# Raspberry_Pi_CM4.net
KiCad netlist of a schematic drawn in Altium Designer
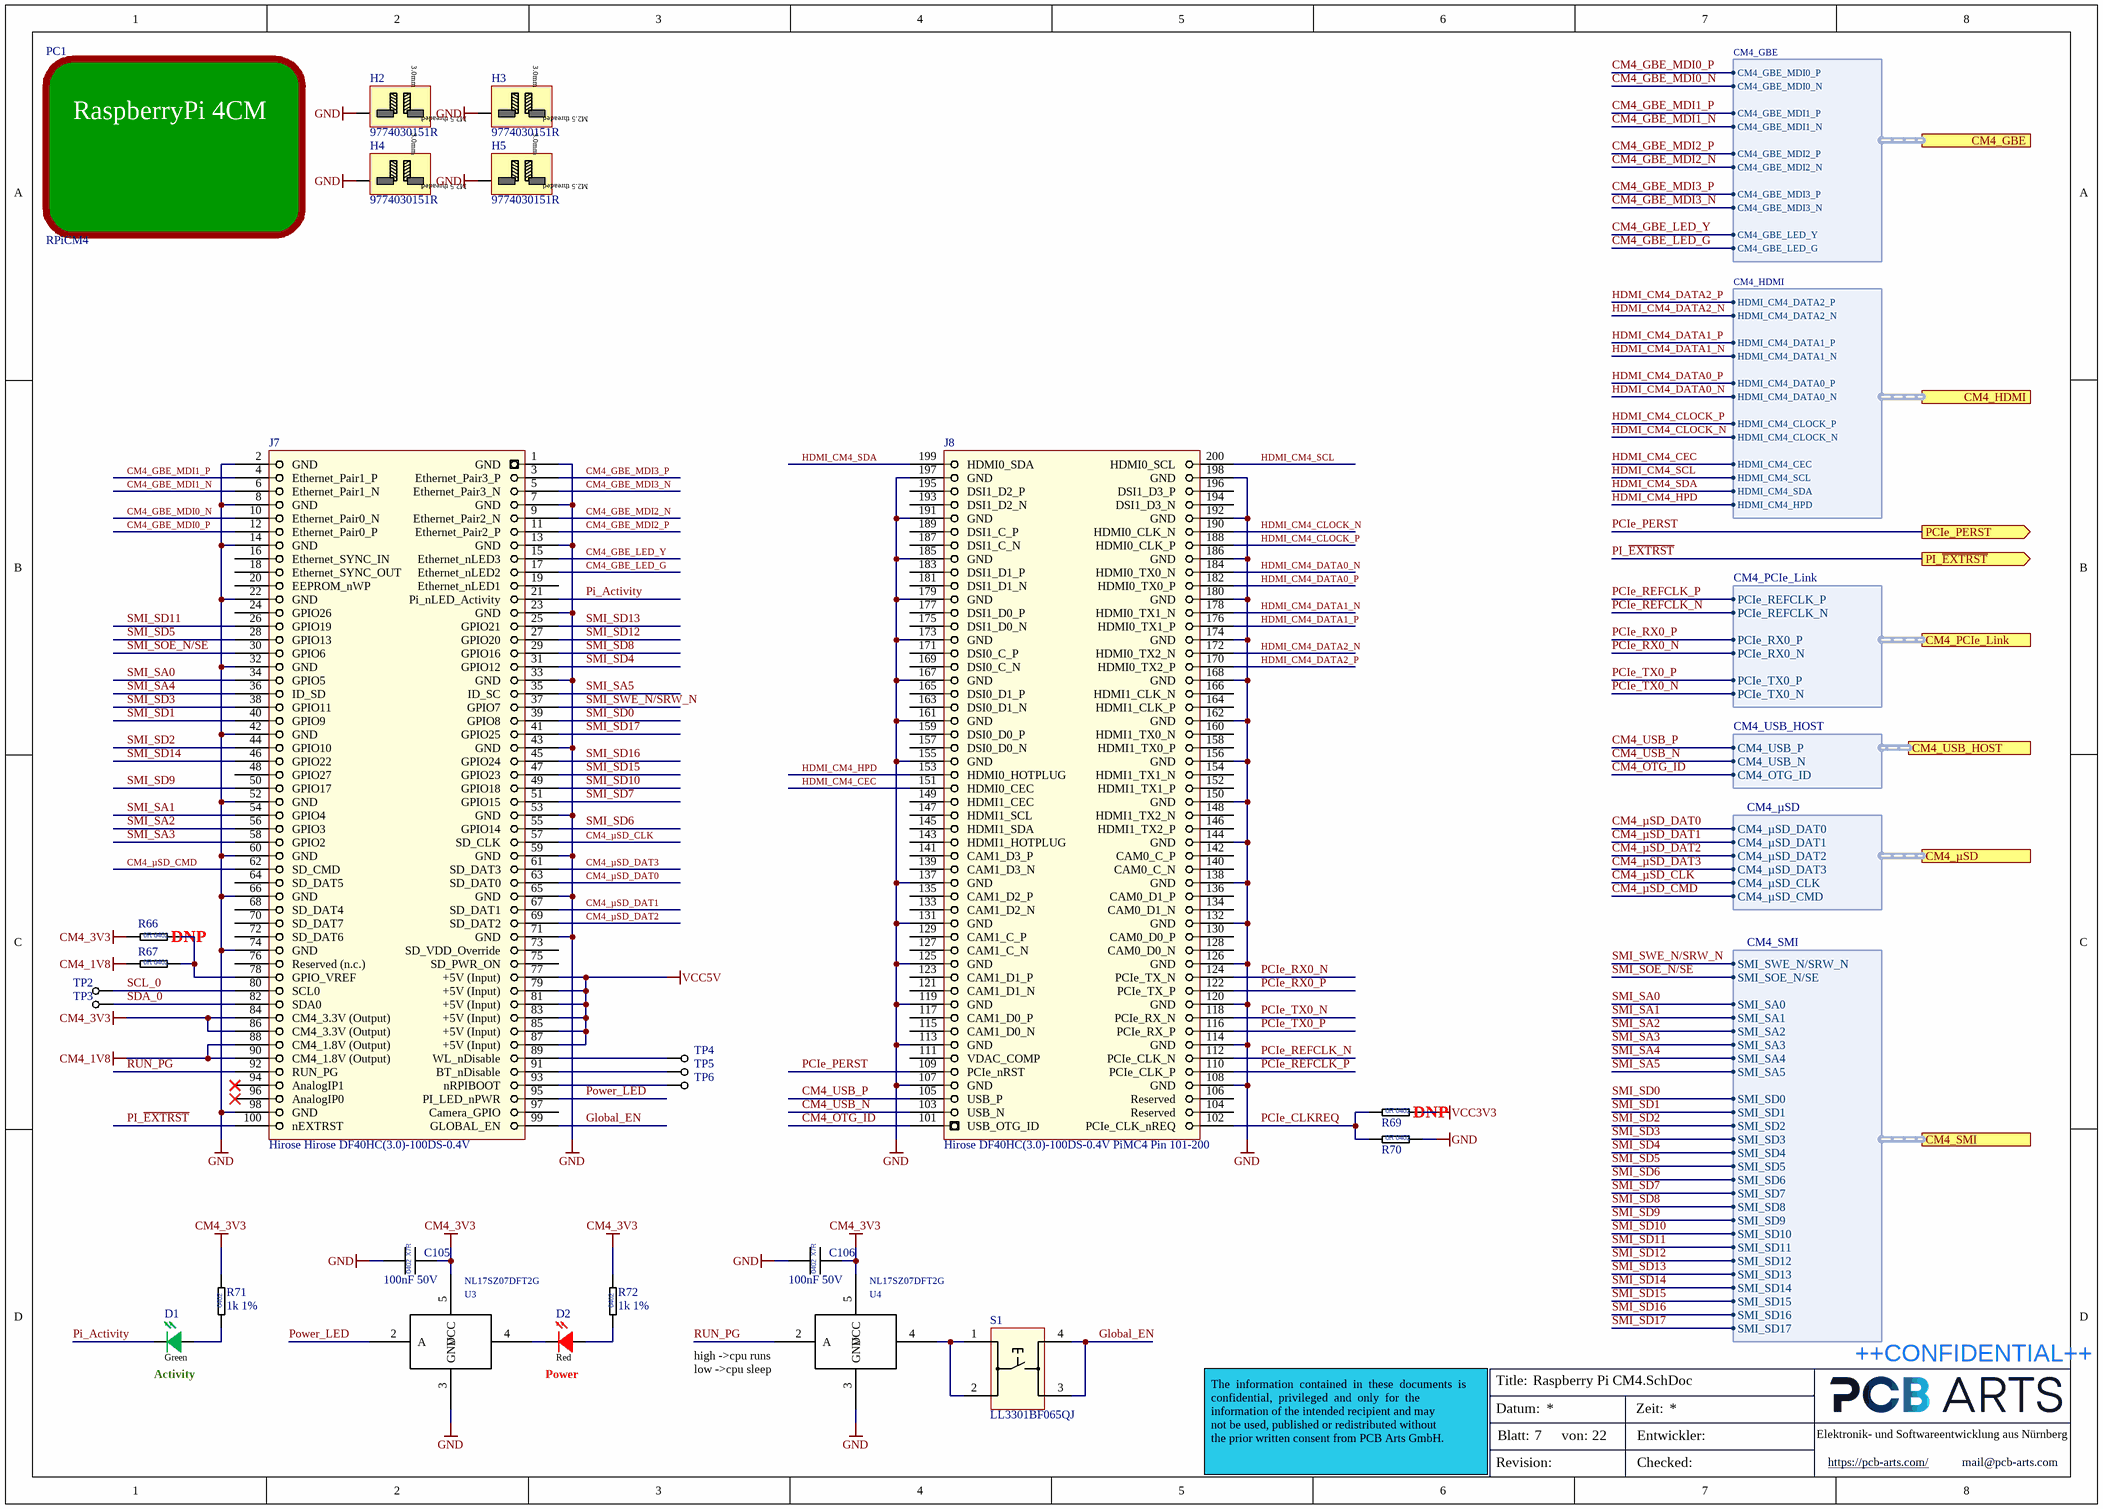
[diagram p0: Raspberry Pi CM4.SchDoc]

(export (version "E")
  (design (tool "Eeschema 10.0.6"))
  (components
    (comp (ref "C105")
      (value "100nF 50V")
      (footprint "Cap:CAP_0402_L")
      (description "Multilayer Ceramic Capacitors MLCC - SMD/SMT 0402 50VDC")
      (libsource (lib "Cap") (part "CAP_0402_100nF_50V"))
    )
    (comp (ref "C106")
      (value "100nF 50V")
      (footprint "Cap:CAP_0402_L")
      (description "Multilayer Ceramic Capacitors MLCC - SMD/SMT 0402 50VDC")
      (libsource (lib "Cap") (part "CAP_0402_100nF_50V"))
    )
    (comp (ref "D1")
      (value "LTST-S270KGKT")
      (footprint "Active:LED-0603 Sideview")
      (description "GREEN  0603 Light Emitting Diode")
      (fields (field (name "COLOR") "Green"))
      (libsource (lib "Active") (part "LED 0603 Green Sideview"))
    )
    (comp (ref "D2")
      (value "LTST-S270KRKT")
      (footprint "Active:LED-0603 Sideview")
      (description "RED  0603 Light Emitting Diode")
      (fields (field (name "COLOR") "Red"))
      (libsource (lib "Active") (part "LED 0603 Red Sideview"))
    )
    (comp (ref "H2")
      (value "9774030151R")
      (footprint "Electro_Mech:9774030151R")
      (description "Würth Standoff M2.5 h:3.0mm 9774030151R")
      (libsource (lib "Electro_Mech") (part "Würth Standoff M2.5 h{colon}3.0mm"))
    )
    (comp (ref "H3")
      (value "9774030151R")
      (footprint "Electro_Mech:9774030151R")
      (description "Würth Standoff M2.5 h:3.0mm 9774030151R")
      (libsource (lib "Electro_Mech") (part "Würth Standoff M2.5 h{colon}3.0mm"))
    )
    (comp (ref "H4")
      (value "9774030151R")
      (footprint "Electro_Mech:9774030151R")
      (description "Würth Standoff M2.5 h:3.0mm 9774030151R")
      (libsource (lib "Electro_Mech") (part "Würth Standoff M2.5 h{colon}3.0mm"))
    )
    (comp (ref "H5")
      (value "9774030151R")
      (footprint "Electro_Mech:9774030151R")
      (description "Würth Standoff M2.5 h:3.0mm 9774030151R")
      (libsource (lib "Electro_Mech") (part "Würth Standoff M2.5 h{colon}3.0mm"))
    )
    (comp (ref "J7")
      (value "Hirose Hirose DF40HC(3.0)-100DS-0.4V")
      (footprint "conn:Hirose DF40HC(3.0)-100DS-0.4V_1-100")
      (description "Hirose DF40HC(3.0)-100DS-0.4V 3mm heigth receptacle for Raspberry Pi CM4, Pin 1-100")
      (libsource (lib "Conn") (part "DF40HC(3.0)-100DS-0.4V RPiCM4 Pin 1-100"))
    )
    (comp (ref "J8")
      (value "Hirose DF40HC(3.0)-100DS-0.4V PiMC4 Pin 101-200")
      (footprint "Conn:Hirose DF40HC(3.0)-100DS-0.4V_101-200")
      (description "Hirose DF40C-100DS-0.4V 3mm heigth receptacle for Raspberry Pi CM4, Pin 101-200")
      (libsource (lib "Conn") (part "DF40HC(3.0)-100DS-0.4V RPiCM4 Pin 101-200"))
    )
    (comp (ref "PC1")
      (value "RPiCM4")
      (footprint "Mechanical:RaspberryPi_CM4")
      (description "Raspberry Pi 4 Compute Module 4")
      (libsource (lib "Mechanical") (part "Raspberry Pi Compute Module 4"))
    )
    (comp (ref "R66")
      (value "0R Jumper")
      (footprint "Res:RES_0402_L")
      (description "Thick Film Resistors - SMD 0Ohm")
      (libsource (lib "Res") (part "RES_0402_0R Jumper"))
    )
    (comp (ref "R67")
      (value "0R Jumper")
      (footprint "Res:RES_0402_L")
      (description "Thick Film Resistors - SMD 0Ohm")
      (libsource (lib "Res") (part "RES_0402_0R Jumper"))
    )
    (comp (ref "R69")
      (value "0R Jumper")
      (footprint "Res:RES_0402_L")
      (description "Thick Film Resistors - SMD 0Ohm")
      (libsource (lib "Res") (part "RES_0402_0R Jumper"))
    )
    (comp (ref "R70")
      (value "0R Jumper")
      (footprint "Res:RES_0402_L")
      (description "Thick Film Resistors - SMD 0Ohm")
      (libsource (lib "Res") (part "RES_0402_0R Jumper"))
    )
    (comp (ref "R71")
      (value "1k 1%")
      (footprint "Res:RES_0402_L")
      (description "Thick Film Resistors - SMD 1kOhm 1%")
      (libsource (lib "Res") (part "RES_0402_1k_1%"))
    )
    (comp (ref "R72")
      (value "1k 1%")
      (footprint "Res:RES_0402_L")
      (description "Thick Film Resistors - SMD 1kOhm 1%")
      (libsource (lib "Res") (part "RES_0402_1k_1%"))
    )
    (comp (ref "S1")
      (value "LL3301BF065QJ")
      (footprint "Electro_Mech:LL3301BF065QJ")
      (description "SPST Top Actuated  Button, 65gf, SMD h: 9.8mm")
      (libsource (lib "Electro_Mech") (part "LL3301BF065QJ_SPST Top Actuated  Button, 65gf, SMD h{colon} 9.8mm"))
    )
    (comp (ref "TP2")
      (value "Testpoint")
      (footprint "Electro_mech:Testpoint 0.8mm")
      (description "Testpoint 0.8mm")
      (libsource (lib "Electro_Mech") (part "Testpoint 0.8mm"))
    )
    (comp (ref "TP3")
      (value "Testpoint")
      (footprint "Electro_mech:Testpoint 0.8mm")
      (description "Testpoint 0.8mm")
      (libsource (lib "Electro_Mech") (part "Testpoint 0.8mm"))
    )
    (comp (ref "TP4")
      (value "Testpoint")
      (footprint "Electro_mech:Testpoint 0.8mm")
      (description "Testpoint 0.8mm")
      (libsource (lib "Electro_Mech") (part "Testpoint 0.8mm"))
    )
    (comp (ref "TP5")
      (value "Testpoint")
      (footprint "Electro_mech:Testpoint 0.8mm")
      (description "Testpoint 0.8mm")
      (libsource (lib "Electro_Mech") (part "Testpoint 0.8mm"))
    )
    (comp (ref "TP6")
      (value "Testpoint")
      (footprint "Electro_mech:Testpoint 0.8mm")
      (description "Testpoint 0.8mm")
      (libsource (lib "Electro_Mech") (part "Testpoint 0.8mm"))
    )
    (comp (ref "U3")
      (value "NL17SZ07DFT2G")
      (footprint "Digital:SOT65P210X110-5N")
      (description "Puffer u. Leitungstreiber 1.65-5.5V Single Non-Inverting")
      (libsource (lib "Digital") (part "NL17SZ07DFT2G_Buffer 1.65-5.5V Single Non-Inverting"))
    )
    (comp (ref "U4")
      (value "NL17SZ07DFT2G")
      (footprint "Digital:SOT65P210X110-5N")
      (description "Puffer u. Leitungstreiber 1.65-5.5V Single Non-Inverting")
      (libsource (lib "Digital") (part "NL17SZ07DFT2G_Buffer 1.65-5.5V Single Non-Inverting"))
    )
  )
  (nets
    (net (code "7") (name "/CM4_GBE_LED_G") (class "Default")
      (node (ref "J7") (pin "17") (pinfunction "Ethernet_nLED2_17") (pintype "passive"))
    )
    (net (code "8") (name "/CM4_GBE_LED_Y") (class "Default")
      (node (ref "J7") (pin "15") (pinfunction "Ethernet_nLED3_15") (pintype "passive"))
    )
    (net (code "9") (name "/CM4_GBE_MDI0_N") (class "Default")
      (node (ref "J7") (pin "10") (pinfunction "Ethernet_Pair0_N_10") (pintype "passive"))
    )
    (net (code "10") (name "/CM4_GBE_MDI0_P") (class "Default")
      (node (ref "J7") (pin "12") (pinfunction "Ethernet_Pair0_P_12") (pintype "passive"))
    )
    (net (code "11") (name "/CM4_GBE_MDI1_N") (class "Default")
      (node (ref "J7") (pin "6") (pinfunction "Ethernet_Pair1_N_6") (pintype "passive"))
    )
    (net (code "12") (name "/CM4_GBE_MDI1_P") (class "Default")
      (node (ref "J7") (pin "4") (pinfunction "Ethernet_Pair1_P_4") (pintype "passive"))
    )
    (net (code "13") (name "/CM4_GBE_MDI2_N") (class "Default")
      (node (ref "J7") (pin "9") (pinfunction "Ethernet_Pair2_N_9") (pintype "passive"))
    )
    (net (code "14") (name "/CM4_GBE_MDI2_P") (class "Default")
      (node (ref "J7") (pin "11") (pinfunction "Ethernet_Pair2_P_11") (pintype "passive"))
    )
    (net (code "15") (name "/CM4_GBE_MDI3_N") (class "Default")
      (node (ref "J7") (pin "5") (pinfunction "Ethernet_Pair3_N_5") (pintype "passive"))
    )
    (net (code "16") (name "/CM4_GBE_MDI3_P") (class "Default")
      (node (ref "J7") (pin "3") (pinfunction "Ethernet_Pair3_P_3") (pintype "passive"))
    )
    (net (code "17") (name "/CM4_OTG_ID") (class "Default")
      (node (ref "J8") (pin "101") (pinfunction "USB_OTG_ID_101") (pintype "passive"))
    )
    (net (code "18") (name "/CM4_USB_N") (class "Default")
      (node (ref "J8") (pin "103") (pinfunction "USB_N_103") (pintype "passive"))
    )
    (net (code "19") (name "/CM4_USB_P") (class "Default")
      (node (ref "J8") (pin "105") (pinfunction "USB_P_105") (pintype "passive"))
    )
    (net (code "20") (name "/CM4_µSD_CLK") (class "Default")
      (node (ref "J7") (pin "57") (pinfunction "SD_CLK_57") (pintype "passive"))
    )
    (net (code "21") (name "/CM4_µSD_CMD") (class "Default")
      (node (ref "J7") (pin "62") (pinfunction "SD_CMD_62") (pintype "passive"))
    )
    (net (code "22") (name "/CM4_µSD_DAT0") (class "Default")
      (node (ref "J7") (pin "63") (pinfunction "SD_DAT0_63") (pintype "passive"))
    )
    (net (code "23") (name "/CM4_µSD_DAT1") (class "Default")
      (node (ref "J7") (pin "67") (pinfunction "SD_DAT1_67") (pintype "passive"))
    )
    (net (code "24") (name "/CM4_µSD_DAT2") (class "Default")
      (node (ref "J7") (pin "69") (pinfunction "SD_DAT2_69") (pintype "passive"))
    )
    (net (code "25") (name "/CM4_µSD_DAT3") (class "Default")
      (node (ref "J7") (pin "61") (pinfunction "SD_DAT3_61") (pintype "passive"))
    )
    (net (code "26") (name "/Global_EN") (class "Default")
      (node (ref "J7") (pin "99") (pinfunction "GLOBAL_EN_99") (pintype "passive"))
      (node (ref "S1") (pin "3") (pinfunction "3_3") (pintype "passive"))
      (node (ref "S1") (pin "4") (pinfunction "4_4") (pintype "passive"))
    )
    (net (code "27") (name "/HDMI_CM4_CEC") (class "Default")
      (node (ref "J8") (pin "151") (pinfunction "HDMI0_CEC_151") (pintype "passive"))
    )
    (net (code "28") (name "/HDMI_CM4_CLOCK_N") (class "Default")
      (node (ref "J8") (pin "190") (pinfunction "HDMI0_CLK_N_190") (pintype "passive"))
    )
    (net (code "29") (name "/HDMI_CM4_CLOCK_P") (class "Default")
      (node (ref "J8") (pin "188") (pinfunction "HDMI0_CLK_P_188") (pintype "passive"))
    )
    (net (code "30") (name "/HDMI_CM4_DATA0_N") (class "Default")
      (node (ref "J8") (pin "184") (pinfunction "HDMI0_TX0_N_184") (pintype "passive"))
    )
    (net (code "31") (name "/HDMI_CM4_DATA0_P") (class "Default")
      (node (ref "J8") (pin "182") (pinfunction "HDMI0_TX0_P_182") (pintype "passive"))
    )
    (net (code "32") (name "/HDMI_CM4_DATA1_N") (class "Default")
      (node (ref "J8") (pin "178") (pinfunction "HDMI0_TX1_N_178") (pintype "passive"))
    )
    (net (code "33") (name "/HDMI_CM4_DATA1_P") (class "Default")
      (node (ref "J8") (pin "176") (pinfunction "HDMI0_TX1_P_176") (pintype "passive"))
    )
    (net (code "34") (name "/HDMI_CM4_DATA2_N") (class "Default")
      (node (ref "J8") (pin "172") (pinfunction "HDMI0_TX2_N_172") (pintype "passive"))
    )
    (net (code "35") (name "/HDMI_CM4_DATA2_P") (class "Default")
      (node (ref "J8") (pin "170") (pinfunction "HDMI0_TX2_P_170") (pintype "passive"))
    )
    (net (code "36") (name "/HDMI_CM4_HPD") (class "Default")
      (node (ref "J8") (pin "153") (pinfunction "HDMI0_HOTPLUG_153") (pintype "passive"))
    )
    (net (code "37") (name "/HDMI_CM4_SCL") (class "Default")
      (node (ref "J8") (pin "200") (pinfunction "HDMI0_SCL_200") (pintype "passive"))
    )
    (net (code "38") (name "/HDMI_CM4_SDA") (class "Default")
      (node (ref "J8") (pin "199") (pinfunction "HDMI0_SDA_199") (pintype "passive"))
    )
    (net (code "39") (name "/PCIe_CLKREQ") (class "Default")
      (node (ref "J8") (pin "102") (pinfunction "PCIe_CLK_nREQ_102") (pintype "passive"))
      (node (ref "R69") (pin "1") (pinfunction "1_1") (pintype "passive"))
      (node (ref "R70") (pin "1") (pinfunction "1_1") (pintype "passive"))
    )
    (net (code "40") (name "/PCIe_PERST") (class "Default")
      (node (ref "J8") (pin "109") (pinfunction "PCIe_nRST_109") (pintype "passive"))
    )
    (net (code "41") (name "/PCIe_REFCLK_N") (class "Default")
      (node (ref "J8") (pin "112") (pinfunction "PCIe_CLK_N_112") (pintype "passive"))
    )
    (net (code "42") (name "/PCIe_REFCLK_P") (class "Default")
      (node (ref "J8") (pin "110") (pinfunction "PCIe_CLK_P_110") (pintype "passive"))
    )
    (net (code "43") (name "/PCIe_RX0_N") (class "Default")
      (node (ref "J8") (pin "124") (pinfunction "PCIe_TX_N_124") (pintype "passive"))
    )
    (net (code "44") (name "/PCIe_RX0_P") (class "Default")
      (node (ref "J8") (pin "122") (pinfunction "PCIe_TX_P_122") (pintype "passive"))
    )
    (net (code "45") (name "/PCIe_TX0_N") (class "Default")
      (node (ref "J8") (pin "118") (pinfunction "PCIe_RX_N_118") (pintype "passive"))
    )
    (net (code "46") (name "/PCIe_TX0_P") (class "Default")
      (node (ref "J8") (pin "116") (pinfunction "PCIe_RX_P_116") (pintype "passive"))
    )
    (net (code "47") (name "/PI_~{EXTRST}") (class "Default")
      (node (ref "J7") (pin "100") (pinfunction "nEXTRST_100") (pintype "passive"))
    )
    (net (code "48") (name "/Pi_Activity") (class "Default")
      (node (ref "D1") (pin "1") (pinfunction "1_1") (pintype "passive"))
      (node (ref "J7") (pin "21") (pinfunction "Pi_nLED_Activity_21") (pintype "passive"))
    )
    (net (code "49") (name "/Power_LED") (class "Default")
      (node (ref "J7") (pin "95") (pinfunction "PI_LED_nPWR_95") (pintype "passive"))
      (node (ref "U3") (pin "2") (pinfunction "A_2") (pintype "passive"))
    )
    (net (code "50") (name "/RUN_PG") (class "Default")
      (node (ref "J7") (pin "92") (pinfunction "RUN_PG_92") (pintype "passive"))
      (node (ref "U4") (pin "2") (pinfunction "A_2") (pintype "passive"))
    )
    (net (code "51") (name "/SCL_0") (class "Default")
      (node (ref "J7") (pin "80") (pinfunction "SCL0_80") (pintype "passive"))
      (node (ref "TP2") (pin "1") (pinfunction "GND_1") (pintype "passive"))
    )
    (net (code "52") (name "/SDA_0") (class "Default")
      (node (ref "J7") (pin "82") (pinfunction "SDA0_82") (pintype "passive"))
      (node (ref "TP3") (pin "1") (pinfunction "GND_1") (pintype "passive"))
    )
    (net (code "53") (name "/SMI_SA0") (class "Default")
      (node (ref "J7") (pin "34") (pinfunction "GPIO5_34") (pintype "passive"))
    )
    (net (code "54") (name "/SMI_SA1") (class "Default")
      (node (ref "J7") (pin "54") (pinfunction "GPIO4_54") (pintype "passive"))
    )
    (net (code "55") (name "/SMI_SA2") (class "Default")
      (node (ref "J7") (pin "56") (pinfunction "GPIO3_56") (pintype "passive"))
    )
    (net (code "56") (name "/SMI_SA3") (class "Default")
      (node (ref "J7") (pin "58") (pinfunction "GPIO2_58") (pintype "passive"))
    )
    (net (code "57") (name "/SMI_SA4") (class "Default")
      (node (ref "J7") (pin "36") (pinfunction "ID_SD_36") (pintype "passive"))
    )
    (net (code "58") (name "/SMI_SA5") (class "Default")
      (node (ref "J7") (pin "35") (pinfunction "ID_SC_35") (pintype "passive"))
    )
    (net (code "59") (name "/SMI_SD0") (class "Default")
      (node (ref "J7") (pin "39") (pinfunction "GPIO8_39") (pintype "passive"))
    )
    (net (code "60") (name "/SMI_SD1") (class "Default")
      (node (ref "J7") (pin "40") (pinfunction "GPIO9_40") (pintype "passive"))
    )
    (net (code "61") (name "/SMI_SD2") (class "Default")
      (node (ref "J7") (pin "44") (pinfunction "GPIO10_44") (pintype "passive"))
    )
    (net (code "62") (name "/SMI_SD3") (class "Default")
      (node (ref "J7") (pin "38") (pinfunction "GPIO11_38") (pintype "passive"))
    )
    (net (code "63") (name "/SMI_SD4") (class "Default")
      (node (ref "J7") (pin "31") (pinfunction "GPIO12_31") (pintype "passive"))
    )
    (net (code "64") (name "/SMI_SD5") (class "Default")
      (node (ref "J7") (pin "28") (pinfunction "GPIO13_28") (pintype "passive"))
    )
    (net (code "65") (name "/SMI_SD6") (class "Default")
      (node (ref "J7") (pin "55") (pinfunction "GPIO14_55") (pintype "passive"))
    )
    (net (code "66") (name "/SMI_SD7") (class "Default")
      (node (ref "J7") (pin "51") (pinfunction "GPIO15_51") (pintype "passive"))
    )
    (net (code "67") (name "/SMI_SD8") (class "Default")
      (node (ref "J7") (pin "29") (pinfunction "GPIO16_29") (pintype "passive"))
    )
    (net (code "68") (name "/SMI_SD9") (class "Default")
      (node (ref "J7") (pin "50") (pinfunction "GPIO17_50") (pintype "passive"))
    )
    (net (code "69") (name "/SMI_SD10") (class "Default")
      (node (ref "J7") (pin "49") (pinfunction "GPIO18_49") (pintype "passive"))
    )
    (net (code "70") (name "/SMI_SD11") (class "Default")
      (node (ref "J7") (pin "26") (pinfunction "GPIO19_26") (pintype "passive"))
    )
    (net (code "71") (name "/SMI_SD12") (class "Default")
      (node (ref "J7") (pin "27") (pinfunction "GPIO20_27") (pintype "passive"))
    )
    (net (code "72") (name "/SMI_SD13") (class "Default")
      (node (ref "J7") (pin "25") (pinfunction "GPIO21_25") (pintype "passive"))
    )
    (net (code "73") (name "/SMI_SD14") (class "Default")
      (node (ref "J7") (pin "46") (pinfunction "GPIO22_46") (pintype "passive"))
    )
    (net (code "74") (name "/SMI_SD15") (class "Default")
      (node (ref "J7") (pin "47") (pinfunction "GPIO23_47") (pintype "passive"))
    )
    (net (code "75") (name "/SMI_SD16") (class "Default")
      (node (ref "J7") (pin "45") (pinfunction "GPIO24_45") (pintype "passive"))
    )
    (net (code "76") (name "/SMI_SD17") (class "Default")
      (node (ref "J7") (pin "41") (pinfunction "GPIO25_41") (pintype "passive"))
    )
    (net (code "77") (name "/SMI_SOE_N{slash}SE") (class "Default")
      (node (ref "J7") (pin "30") (pinfunction "GPIO6_30") (pintype "passive"))
    )
    (net (code "78") (name "/SMI_SWE_N{slash}SRW_N") (class "Default")
      (node (ref "J7") (pin "37") (pinfunction "GPIO7_37") (pintype "passive"))
    )
    (net (code "85") (name "CM4_1V8") (class "Default")
      (node (ref "J7") (pin "88") (pinfunction "CM4_1.8V_(Output)_88") (pintype "passive"))
      (node (ref "J7") (pin "90") (pinfunction "CM4_1.8V_(Output)_90") (pintype "passive"))
      (node (ref "R67") (pin "1") (pinfunction "1_1") (pintype "passive"))
    )
    (net (code "86") (name "CM4_3V3") (class "Default")
      (node (ref "C105") (pin "2") (pinfunction "2_2") (pintype "passive"))
      (node (ref "C106") (pin "2") (pinfunction "2_2") (pintype "passive"))
      (node (ref "J7") (pin "84") (pinfunction "CM4_3.3V_(Output)_84") (pintype "passive"))
      (node (ref "J7") (pin "86") (pinfunction "CM4_3.3V_(Output)_86") (pintype "passive"))
      (node (ref "R66") (pin "1") (pinfunction "1_1") (pintype "passive"))
      (node (ref "R71") (pin "2") (pinfunction "2_2") (pintype "passive"))
      (node (ref "R72") (pin "2") (pinfunction "2_2") (pintype "passive"))
      (node (ref "U3") (pin "5") (pinfunction "VCC_5") (pintype "passive"))
      (node (ref "U4") (pin "5") (pinfunction "VCC_5") (pintype "passive"))
    )
    (net (code "87") (name "GND") (class "Default")
      (node (ref "C105") (pin "1") (pinfunction "1_1") (pintype "passive"))
      (node (ref "C106") (pin "1") (pinfunction "1_1") (pintype "passive"))
      (node (ref "H2") (pin "1") (pinfunction "1_1") (pintype "passive"))
      (node (ref "H3") (pin "1") (pinfunction "1_1") (pintype "passive"))
      (node (ref "H4") (pin "1") (pinfunction "1_1") (pintype "passive"))
      (node (ref "H5") (pin "1") (pinfunction "1_1") (pintype "passive"))
      (node (ref "J7") (pin "1") (pinfunction "GND_1") (pintype "passive"))
      (node (ref "J7") (pin "13") (pinfunction "GND_13") (pintype "passive"))
      (node (ref "J7") (pin "14") (pinfunction "GND_14") (pintype "passive"))
      (node (ref "J7") (pin "2") (pinfunction "GND_2") (pintype "passive"))
      (node (ref "J7") (pin "22") (pinfunction "GND_22") (pintype "passive"))
      (node (ref "J7") (pin "23") (pinfunction "GND_23") (pintype "passive"))
      (node (ref "J7") (pin "32") (pinfunction "GND_32") (pintype "passive"))
      (node (ref "J7") (pin "33") (pinfunction "GND_33") (pintype "passive"))
      (node (ref "J7") (pin "42") (pinfunction "GND_42") (pintype "passive"))
      (node (ref "J7") (pin "43") (pinfunction "GND_43") (pintype "passive"))
      (node (ref "J7") (pin "52") (pinfunction "GND_52") (pintype "passive"))
      (node (ref "J7") (pin "53") (pinfunction "GND_53") (pintype "passive"))
      (node (ref "J7") (pin "59") (pinfunction "GND_59") (pintype "passive"))
      (node (ref "J7") (pin "60") (pinfunction "GND_60") (pintype "passive"))
      (node (ref "J7") (pin "65") (pinfunction "GND_65") (pintype "passive"))
      (node (ref "J7") (pin "66") (pinfunction "GND_66") (pintype "passive"))
      (node (ref "J7") (pin "7") (pinfunction "GND_7") (pintype "passive"))
      (node (ref "J7") (pin "71") (pinfunction "GND_71") (pintype "passive"))
      (node (ref "J7") (pin "74") (pinfunction "GND_74") (pintype "passive"))
      (node (ref "J7") (pin "8") (pinfunction "GND_8") (pintype "passive"))
      (node (ref "J7") (pin "98") (pinfunction "GND_98") (pintype "passive"))
      (node (ref "J8") (pin "107") (pinfunction "GND_107") (pintype "passive"))
      (node (ref "J8") (pin "108") (pinfunction "GND_108") (pintype "passive"))
      (node (ref "J8") (pin "113") (pinfunction "GND_113") (pintype "passive"))
      (node (ref "J8") (pin "114") (pinfunction "GND_114") (pintype "passive"))
      (node (ref "J8") (pin "119") (pinfunction "GND_119") (pintype "passive"))
      (node (ref "J8") (pin "120") (pinfunction "GND_120") (pintype "passive"))
      (node (ref "J8") (pin "125") (pinfunction "GND_125") (pintype "passive"))
      (node (ref "J8") (pin "126") (pinfunction "GND_126") (pintype "passive"))
      (node (ref "J8") (pin "131") (pinfunction "GND_131") (pintype "passive"))
      (node (ref "J8") (pin "132") (pinfunction "GND_132") (pintype "passive"))
      (node (ref "J8") (pin "137") (pinfunction "GND_137") (pintype "passive"))
      (node (ref "J8") (pin "138") (pinfunction "GND_138") (pintype "passive"))
      (node (ref "J8") (pin "144") (pinfunction "GND_144") (pintype "passive"))
      (node (ref "J8") (pin "150") (pinfunction "GND_150") (pintype "passive"))
      (node (ref "J8") (pin "155") (pinfunction "GND_155") (pintype "passive"))
      (node (ref "J8") (pin "156") (pinfunction "GND_156") (pintype "passive"))
      (node (ref "J8") (pin "161") (pinfunction "GND_161") (pintype "passive"))
      (node (ref "J8") (pin "162") (pinfunction "GND_162") (pintype "passive"))
      (node (ref "J8") (pin "167") (pinfunction "GND_167") (pintype "passive"))
      (node (ref "J8") (pin "168") (pinfunction "GND_168") (pintype "passive"))
      (node (ref "J8") (pin "173") (pinfunction "GND_173") (pintype "passive"))
      (node (ref "J8") (pin "174") (pinfunction "GND_174") (pintype "passive"))
      (node (ref "J8") (pin "179") (pinfunction "GND_179") (pintype "passive"))
      (node (ref "J8") (pin "180") (pinfunction "GND_180") (pintype "passive"))
      (node (ref "J8") (pin "185") (pinfunction "GND_185") (pintype "passive"))
      (node (ref "J8") (pin "186") (pinfunction "GND_186") (pintype "passive"))
      (node (ref "J8") (pin "191") (pinfunction "GND_191") (pintype "passive"))
      (node (ref "J8") (pin "192") (pinfunction "GND_192") (pintype "passive"))
      (node (ref "J8") (pin "197") (pinfunction "GND_197") (pintype "passive"))
      (node (ref "J8") (pin "198") (pinfunction "GND_198") (pintype "passive"))
      (node (ref "R70") (pin "2") (pinfunction "2_2") (pintype "passive"))
      (node (ref "U3") (pin "3") (pinfunction "GND_3") (pintype "passive"))
      (node (ref "U4") (pin "3") (pinfunction "GND_3") (pintype "passive"))
    )
    (net (code "88") (name "Net-(D1-Pad2)") (class "Default")
      (node (ref "D1") (pin "2") (pinfunction "2_2") (pintype "passive"))
      (node (ref "R71") (pin "1") (pinfunction "1_1") (pintype "passive"))
    )
    (net (code "89") (name "Net-(D2-Pad2)") (class "Default")
      (node (ref "D2") (pin "2") (pinfunction "2_2") (pintype "passive"))
      (node (ref "R72") (pin "1") (pinfunction "1_1") (pintype "passive"))
    )
    (net (code "90") (name "Net-(J7-BT_nDisable)") (class "Default")
      (node (ref "J7") (pin "91") (pinfunction "BT_nDisable_91") (pintype "passive"))
      (node (ref "TP5") (pin "1") (pinfunction "GND_1") (pintype "passive"))
    )
    (net (code "91") (name "Net-(J7-GPIO_VREF)") (class "Default")
      (node (ref "J7") (pin "78") (pinfunction "GPIO_VREF_78") (pintype "passive"))
      (node (ref "R66") (pin "2") (pinfunction "2_2") (pintype "passive"))
      (node (ref "R67") (pin "2") (pinfunction "2_2") (pintype "passive"))
    )
    (net (code "92") (name "Net-(J7-WL_nDisable)") (class "Default")
      (node (ref "J7") (pin "89") (pinfunction "WL_nDisable_89") (pintype "passive"))
      (node (ref "TP4") (pin "1") (pinfunction "GND_1") (pintype "passive"))
    )
    (net (code "93") (name "Net-(J7-nRPIBOOT)") (class "Default")
      (node (ref "J7") (pin "93") (pinfunction "nRPIBOOT_93") (pintype "passive"))
      (node (ref "TP6") (pin "1") (pinfunction "GND_1") (pintype "passive"))
    )
    (net (code "94") (name "Net-(U3-Y)") (class "Default")
      (node (ref "D2") (pin "1") (pinfunction "1_1") (pintype "passive"))
      (node (ref "U3") (pin "4") (pinfunction "Y_4") (pintype "passive"))
    )
    (net (code "95") (name "Net-(U4-Y)") (class "Default")
      (node (ref "S1") (pin "1") (pinfunction "1_1") (pintype "passive"))
      (node (ref "S1") (pin "2") (pinfunction "2_2") (pintype "passive"))
      (node (ref "U4") (pin "4") (pinfunction "Y_4") (pintype "passive"))
    )
    (net (code "96") (name "VCC3V3") (class "Default")
      (node (ref "R69") (pin "2") (pinfunction "2_2") (pintype "passive"))
    )
    (net (code "97") (name "VCC5V") (class "Default")
      (node (ref "J7") (pin "77") (pinfunction "+5V_(Input)_77") (pintype "passive"))
      (node (ref "J7") (pin "79") (pinfunction "+5V_(Input)_79") (pintype "passive"))
      (node (ref "J7") (pin "81") (pinfunction "+5V_(Input)_81") (pintype "passive"))
      (node (ref "J7") (pin "83") (pinfunction "+5V_(Input)_83") (pintype "passive"))
      (node (ref "J7") (pin "85") (pinfunction "+5V_(Input)_85") (pintype "passive"))
      (node (ref "J7") (pin "87") (pinfunction "+5V_(Input)_87") (pintype "passive"))
    )
    (net (code "98") (name "unconnected-(J7-AnalogIP0-Pad96)") (class "Default")
      (node (ref "J7") (pin "96") (pinfunction "AnalogIP0_96") (pintype "passive+no_connect"))
    )
    (net (code "99") (name "unconnected-(J7-AnalogIP1-Pad94)") (class "Default")
      (node (ref "J7") (pin "94") (pinfunction "AnalogIP1_94") (pintype "passive+no_connect"))
    )
    (net (code "100") (name "unconnected-(J7-Camera_GPIO-Pad97)") (class "Default")
      (node (ref "J7") (pin "97") (pinfunction "Camera_GPIO_97") (pintype "passive"))
    )
    (net (code "101") (name "unconnected-(J7-EEPROM_nWP-Pad20)") (class "Default")
      (node (ref "J7") (pin "20") (pinfunction "EEPROM_nWP_20") (pintype "passive"))
    )
    (net (code "102") (name "unconnected-(J7-Ethernet_SYNC_IN-Pad16)") (class "Default")
      (node (ref "J7") (pin "16") (pinfunction "Ethernet_SYNC_IN_16") (pintype "passive"))
    )
    (net (code "103") (name "unconnected-(J7-Ethernet_SYNC_OUT-Pad18)") (class "Default")
      (node (ref "J7") (pin "18") (pinfunction "Ethernet_SYNC_OUT_18") (pintype "passive"))
    )
    (net (code "104") (name "unconnected-(J7-Ethernet_nLED1-Pad19)") (class "Default")
      (node (ref "J7") (pin "19") (pinfunction "Ethernet_nLED1_19") (pintype "passive"))
    )
    (net (code "105") (name "unconnected-(J7-GPIO26-Pad24)") (class "Default")
      (node (ref "J7") (pin "24") (pinfunction "GPIO26_24") (pintype "passive"))
    )
    (net (code "106") (name "unconnected-(J7-GPIO27-Pad48)") (class "Default")
      (node (ref "J7") (pin "48") (pinfunction "GPIO27_48") (pintype "passive"))
    )
    (net (code "107") (name "unconnected-(J7-Reserved_(n.c.)-Pad76)") (class "Default")
      (node (ref "J7") (pin "76") (pinfunction "Reserved_(n.c.)_76") (pintype "passive"))
    )
    (net (code "108") (name "unconnected-(J7-SD_DAT4-Pad68)") (class "Default")
      (node (ref "J7") (pin "68") (pinfunction "SD_DAT4_68") (pintype "passive"))
    )
    (net (code "109") (name "unconnected-(J7-SD_DAT5-Pad64)") (class "Default")
      (node (ref "J7") (pin "64") (pinfunction "SD_DAT5_64") (pintype "passive"))
    )
    (net (code "110") (name "unconnected-(J7-SD_DAT6-Pad72)") (class "Default")
      (node (ref "J7") (pin "72") (pinfunction "SD_DAT6_72") (pintype "passive"))
    )
    (net (code "111") (name "unconnected-(J7-SD_DAT7-Pad70)") (class "Default")
      (node (ref "J7") (pin "70") (pinfunction "SD_DAT7_70") (pintype "passive"))
    )
    (net (code "112") (name "unconnected-(J7-SD_PWR_ON-Pad75)") (class "Default")
      (node (ref "J7") (pin "75") (pinfunction "SD_PWR_ON_75") (pintype "passive"))
    )
    (net (code "113") (name "unconnected-(J7-SD_VDD_Override-Pad73)") (class "Default")
      (node (ref "J7") (pin "73") (pinfunction "SD_VDD_Override_73") (pintype "passive"))
    )
    (net (code "114") (name "unconnected-(J8-CAM0_C_N-Pad140)") (class "Default")
      (node (ref "J8") (pin "140") (pinfunction "CAM0_C_N_140") (pintype "passive"))
    )
    (net (code "115") (name "unconnected-(J8-CAM0_C_P-Pad142)") (class "Default")
      (node (ref "J8") (pin "142") (pinfunction "CAM0_C_P_142") (pintype "passive"))
    )
    (net (code "116") (name "unconnected-(J8-CAM0_D0_N-Pad128)") (class "Default")
      (node (ref "J8") (pin "128") (pinfunction "CAM0_D0_N_128") (pintype "passive"))
    )
    (net (code "117") (name "unconnected-(J8-CAM0_D0_P-Pad130)") (class "Default")
      (node (ref "J8") (pin "130") (pinfunction "CAM0_D0_P_130") (pintype "passive"))
    )
    (net (code "118") (name "unconnected-(J8-CAM0_D1_N-Pad134)") (class "Default")
      (node (ref "J8") (pin "134") (pinfunction "CAM0_D1_N_134") (pintype "passive"))
    )
    (net (code "119") (name "unconnected-(J8-CAM0_D1_P-Pad136)") (class "Default")
      (node (ref "J8") (pin "136") (pinfunction "CAM0_D1_P_136") (pintype "passive"))
    )
    (net (code "120") (name "unconnected-(J8-CAM1_C_N-Pad127)") (class "Default")
      (node (ref "J8") (pin "127") (pinfunction "CAM1_C_N_127") (pintype "passive"))
    )
    (net (code "121") (name "unconnected-(J8-CAM1_C_P-Pad129)") (class "Default")
      (node (ref "J8") (pin "129") (pinfunction "CAM1_C_P_129") (pintype "passive"))
    )
    (net (code "122") (name "unconnected-(J8-CAM1_D0_N-Pad115)") (class "Default")
      (node (ref "J8") (pin "115") (pinfunction "CAM1_D0_N_115") (pintype "passive"))
    )
    (net (code "123") (name "unconnected-(J8-CAM1_D0_P-Pad117)") (class "Default")
      (node (ref "J8") (pin "117") (pinfunction "CAM1_D0_P_117") (pintype "passive"))
    )
    (net (code "124") (name "unconnected-(J8-CAM1_D1_N-Pad121)") (class "Default")
      (node (ref "J8") (pin "121") (pinfunction "CAM1_D1_N_121") (pintype "passive"))
    )
    (net (code "125") (name "unconnected-(J8-CAM1_D1_P-Pad123)") (class "Default")
      (node (ref "J8") (pin "123") (pinfunction "CAM1_D1_P_123") (pintype "passive"))
    )
    (net (code "126") (name "unconnected-(J8-CAM1_D2_N-Pad133)") (class "Default")
      (node (ref "J8") (pin "133") (pinfunction "CAM1_D2_N_133") (pintype "passive"))
    )
    (net (code "127") (name "unconnected-(J8-CAM1_D2_P-Pad135)") (class "Default")
      (node (ref "J8") (pin "135") (pinfunction "CAM1_D2_P_135") (pintype "passive"))
    )
    (net (code "128") (name "unconnected-(J8-CAM1_D3_N-Pad139)") (class "Default")
      (node (ref "J8") (pin "139") (pinfunction "CAM1_D3_N_139") (pintype "passive"))
    )
    (net (code "129") (name "unconnected-(J8-CAM1_D3_P-Pad141)") (class "Default")
      (node (ref "J8") (pin "141") (pinfunction "CAM1_D3_P_141") (pintype "passive"))
    )
    (net (code "130") (name "unconnected-(J8-DSI0_C_N-Pad169)") (class "Default")
      (node (ref "J8") (pin "169") (pinfunction "DSI0_C_N_169") (pintype "passive"))
    )
    (net (code "131") (name "unconnected-(J8-DSI0_C_P-Pad171)") (class "Default")
      (node (ref "J8") (pin "171") (pinfunction "DSI0_C_P_171") (pintype "passive"))
    )
    (net (code "132") (name "unconnected-(J8-DSI0_D0_N-Pad157)") (class "Default")
      (node (ref "J8") (pin "157") (pinfunction "DSI0_D0_N_157") (pintype "passive"))
    )
    (net (code "133") (name "unconnected-(J8-DSI0_D0_P-Pad159)") (class "Default")
      (node (ref "J8") (pin "159") (pinfunction "DSI0_D0_P_159") (pintype "passive"))
    )
    (net (code "134") (name "unconnected-(J8-DSI0_D1_N-Pad163)") (class "Default")
      (node (ref "J8") (pin "163") (pinfunction "DSI0_D1_N_163") (pintype "passive"))
    )
    (net (code "135") (name "unconnected-(J8-DSI0_D1_P-Pad165)") (class "Default")
      (node (ref "J8") (pin "165") (pinfunction "DSI0_D1_P_165") (pintype "passive"))
    )
    (net (code "136") (name "unconnected-(J8-DSI1_C_N-Pad187)") (class "Default")
      (node (ref "J8") (pin "187") (pinfunction "DSI1_C_N_187") (pintype "passive"))
    )
    (net (code "137") (name "unconnected-(J8-DSI1_C_P-Pad189)") (class "Default")
      (node (ref "J8") (pin "189") (pinfunction "DSI1_C_P_189") (pintype "passive"))
    )
    (net (code "138") (name "unconnected-(J8-DSI1_D0_N-Pad175)") (class "Default")
      (node (ref "J8") (pin "175") (pinfunction "DSI1_D0_N_175") (pintype "passive"))
    )
    (net (code "139") (name "unconnected-(J8-DSI1_D0_P-Pad177)") (class "Default")
      (node (ref "J8") (pin "177") (pinfunction "DSI1_D0_P_177") (pintype "passive"))
    )
    (net (code "140") (name "unconnected-(J8-DSI1_D1_N-Pad181)") (class "Default")
      (node (ref "J8") (pin "181") (pinfunction "DSI1_D1_N_181") (pintype "passive"))
    )
    (net (code "141") (name "unconnected-(J8-DSI1_D1_P-Pad183)") (class "Default")
      (node (ref "J8") (pin "183") (pinfunction "DSI1_D1_P_183") (pintype "passive"))
    )
    (net (code "142") (name "unconnected-(J8-DSI1_D2_N-Pad193)") (class "Default")
      (node (ref "J8") (pin "193") (pinfunction "DSI1_D2_N_193") (pintype "passive"))
    )
    (net (code "143") (name "unconnected-(J8-DSI1_D2_P-Pad195)") (class "Default")
      (node (ref "J8") (pin "195") (pinfunction "DSI1_D2_P_195") (pintype "passive"))
    )
    (net (code "144") (name "unconnected-(J8-DSI1_D3_N-Pad194)") (class "Default")
      (node (ref "J8") (pin "194") (pinfunction "DSI1_D3_N_194") (pintype "passive"))
    )
    (net (code "145") (name "unconnected-(J8-DSI1_D3_P-Pad196)") (class "Default")
      (node (ref "J8") (pin "196") (pinfunction "DSI1_D3_P_196") (pintype "passive"))
    )
    (net (code "146") (name "unconnected-(J8-HDMI1_CEC-Pad149)") (class "Default")
      (node (ref "J8") (pin "149") (pinfunction "HDMI1_CEC_149") (pintype "passive"))
    )
    (net (code "147") (name "unconnected-(J8-HDMI1_CLK_N-Pad166)") (class "Default")
      (node (ref "J8") (pin "166") (pinfunction "HDMI1_CLK_N_166") (pintype "passive"))
    )
    (net (code "148") (name "unconnected-(J8-HDMI1_CLK_P-Pad164)") (class "Default")
      (node (ref "J8") (pin "164") (pinfunction "HDMI1_CLK_P_164") (pintype "passive"))
    )
    (net (code "149") (name "unconnected-(J8-HDMI1_HOTPLUG-Pad143)") (class "Default")
      (node (ref "J8") (pin "143") (pinfunction "HDMI1_HOTPLUG_143") (pintype "passive"))
    )
    (net (code "150") (name "unconnected-(J8-HDMI1_SCL-Pad147)") (class "Default")
      (node (ref "J8") (pin "147") (pinfunction "HDMI1_SCL_147") (pintype "passive"))
    )
    (net (code "151") (name "unconnected-(J8-HDMI1_SDA-Pad145)") (class "Default")
      (node (ref "J8") (pin "145") (pinfunction "HDMI1_SDA_145") (pintype "passive"))
    )
    (net (code "152") (name "unconnected-(J8-HDMI1_TX0_N-Pad160)") (class "Default")
      (node (ref "J8") (pin "160") (pinfunction "HDMI1_TX0_N_160") (pintype "passive"))
    )
    (net (code "153") (name "unconnected-(J8-HDMI1_TX0_P-Pad158)") (class "Default")
      (node (ref "J8") (pin "158") (pinfunction "HDMI1_TX0_P_158") (pintype "passive"))
    )
    (net (code "154") (name "unconnected-(J8-HDMI1_TX1_N-Pad154)") (class "Default")
      (node (ref "J8") (pin "154") (pinfunction "HDMI1_TX1_N_154") (pintype "passive"))
    )
    (net (code "155") (name "unconnected-(J8-HDMI1_TX1_P-Pad152)") (class "Default")
      (node (ref "J8") (pin "152") (pinfunction "HDMI1_TX1_P_152") (pintype "passive"))
    )
    (net (code "156") (name "unconnected-(J8-HDMI1_TX2_N-Pad148)") (class "Default")
      (node (ref "J8") (pin "148") (pinfunction "HDMI1_TX2_N_148") (pintype "passive"))
    )
    (net (code "157") (name "unconnected-(J8-HDMI1_TX2_P-Pad146)") (class "Default")
      (node (ref "J8") (pin "146") (pinfunction "HDMI1_TX2_P_146") (pintype "passive"))
    )
    (net (code "158") (name "unconnected-(J8-Reserved-Pad104)") (class "Default")
      (node (ref "J8") (pin "104") (pinfunction "Reserved_104") (pintype "passive"))
    )
    (net (code "159") (name "unconnected-(J8-Reserved-Pad106)") (class "Default")
      (node (ref "J8") (pin "106") (pinfunction "Reserved_106") (pintype "passive"))
    )
    (net (code "160") (name "unconnected-(J8-VDAC_COMP-Pad111)") (class "Default")
      (node (ref "J8") (pin "111") (pinfunction "VDAC_COMP_111") (pintype "passive"))
    )
  )
)
